# HBridges.net
KiCad netlist of a schematic drawn in Altium Designer
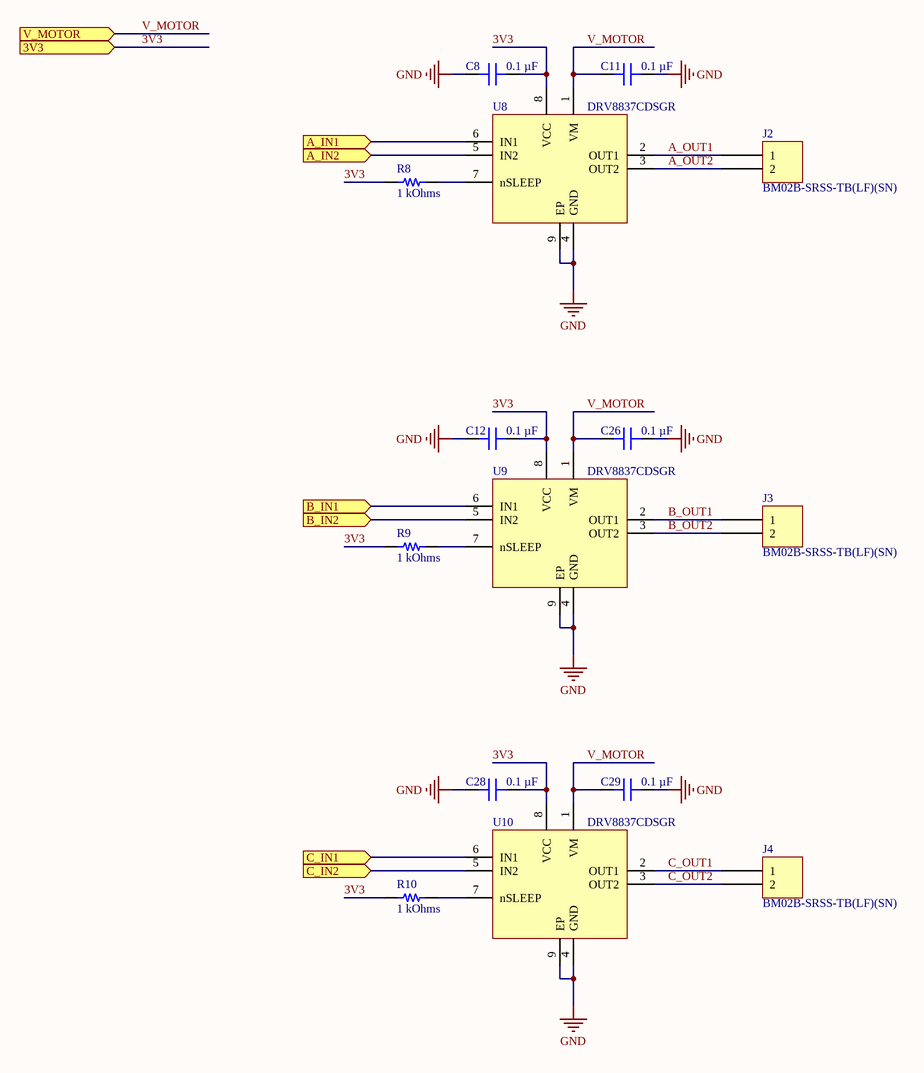
[diagram p0: HBridges.SchDoc]

(export (version "E")
  (design (tool "Eeschema 10.0.6"))
  (components
    (comp (ref "C8")
      (value "0.1 µF")
      (footprint "CAP 0402_1005")
      (description "CAP CER 0.1UF 16V X7R 0402")
      (fields (field (name "PART NUMBER") "C0402C104K4RACAUTO") (field (name "MANUFACTURER") "KEMET"))
      (libsource (lib "Celestial Altium Library - altium_library") (part "Capacitor"))
    )
    (comp (ref "C11")
      (value "0.1 µF")
      (footprint "CAP 0402_1005")
      (description "CAP CER 0.1UF 16V X7R 0402")
      (fields (field (name "PART NUMBER") "C0402C104K4RACAUTO") (field (name "MANUFACTURER") "KEMET"))
      (libsource (lib "Celestial Altium Library - altium_library") (part "Capacitor"))
    )
    (comp (ref "C12")
      (value "0.1 µF")
      (footprint "CAP 0402_1005")
      (description "CAP CER 0.1UF 16V X7R 0402")
      (fields (field (name "PART NUMBER") "C0402C104K4RACAUTO") (field (name "MANUFACTURER") "KEMET"))
      (libsource (lib "Celestial Altium Library - altium_library") (part "Capacitor"))
    )
    (comp (ref "C26")
      (value "0.1 µF")
      (footprint "CAP 0402_1005")
      (description "CAP CER 0.1UF 16V X7R 0402")
      (fields (field (name "PART NUMBER") "C0402C104K4RACAUTO") (field (name "MANUFACTURER") "KEMET"))
      (libsource (lib "Celestial Altium Library - altium_library") (part "Capacitor"))
    )
    (comp (ref "C28")
      (value "0.1 µF")
      (footprint "CAP 0402_1005")
      (description "CAP CER 0.1UF 16V X7R 0402")
      (fields (field (name "PART NUMBER") "C0402C104K4RACAUTO") (field (name "MANUFACTURER") "KEMET"))
      (libsource (lib "Celestial Altium Library - altium_library") (part "Capacitor"))
    )
    (comp (ref "C29")
      (value "0.1 µF")
      (footprint "CAP 0402_1005")
      (description "CAP CER 0.1UF 16V X7R 0402")
      (fields (field (name "PART NUMBER") "C0402C104K4RACAUTO") (field (name "MANUFACTURER") "KEMET"))
      (libsource (lib "Celestial Altium Library - altium_library") (part "Capacitor"))
    )
    (comp (ref "J2")
      (value "BM02B-SRSS-TB(LF)(SN)")
      (footprint "JST BM02B-SRSS-TB")
      (description "CONN HEADER SMD 2POS 1MM")
      (fields (field (name "MANUFACTURER") "JST Sales America Inc."))
      (libsource (lib "Celestial Altium Library - altium_library") (part "2 Pin"))
    )
    (comp (ref "J3")
      (value "BM02B-SRSS-TB(LF)(SN)")
      (footprint "JST BM02B-SRSS-TB")
      (description "CONN HEADER SMD 2POS 1MM")
      (fields (field (name "MANUFACTURER") "JST Sales America Inc."))
      (libsource (lib "Celestial Altium Library - altium_library") (part "2 Pin"))
    )
    (comp (ref "J4")
      (value "BM02B-SRSS-TB(LF)(SN)")
      (footprint "JST BM02B-SRSS-TB")
      (description "CONN HEADER SMD 2POS 1MM")
      (fields (field (name "MANUFACTURER") "JST Sales America Inc."))
      (libsource (lib "Celestial Altium Library - altium_library") (part "2 Pin"))
    )
    (comp (ref "R8")
      (value "1 kOhms")
      (footprint "YAGEO RES 0402_1005")
      (description "RES 1K OHM 1% 1/16W 0402")
      (fields (field (name "PART NUMBER") "RC0402FR-071KL") (field (name "MANUFACTURER") "Yageo"))
      (libsource (lib "Celestial Altium Library - altium_library") (part "Resistor"))
    )
    (comp (ref "R9")
      (value "1 kOhms")
      (footprint "YAGEO RES 0402_1005")
      (description "RES 1K OHM 1% 1/16W 0402")
      (fields (field (name "PART NUMBER") "RC0402FR-071KL") (field (name "MANUFACTURER") "Yageo"))
      (libsource (lib "Celestial Altium Library - altium_library") (part "Resistor"))
    )
    (comp (ref "R10")
      (value "1 kOhms")
      (footprint "YAGEO RES 0402_1005")
      (description "RES 1K OHM 1% 1/16W 0402")
      (fields (field (name "PART NUMBER") "RC0402FR-071KL") (field (name "MANUFACTURER") "Yageo"))
      (libsource (lib "Celestial Altium Library - altium_library") (part "Resistor"))
    )
    (comp (ref "U8")
      (value "DRV8837CDSGR")
      (footprint "SON50P200X200X80-9N")
      (description "11-V, 1-A H-bridge motor driver 8-WSON -40 to 85")
      (fields (field (name "MF") "Texas Instruments"))
      (libsource (lib "IC") (part "DRV8837CDSGR"))
    )
    (comp (ref "U9")
      (value "DRV8837CDSGR")
      (footprint "SON50P200X200X80-9N")
      (description "11-V, 1-A H-bridge motor driver 8-WSON -40 to 85")
      (fields (field (name "MF") "Texas Instruments"))
      (libsource (lib "IC") (part "DRV8837CDSGR"))
    )
    (comp (ref "U10")
      (value "DRV8837CDSGR")
      (footprint "SON50P200X200X80-9N")
      (description "11-V, 1-A H-bridge motor driver 8-WSON -40 to 85")
      (fields (field (name "MF") "Texas Instruments"))
      (libsource (lib "IC") (part "DRV8837CDSGR"))
    )
  )
  (nets
    (net (code "1") (name "/3V3") (class "Default")
      (node (ref "C12") (pin "1") (pinfunction "1_1") (pintype "passive"))
      (node (ref "C28") (pin "1") (pinfunction "1_1") (pintype "passive"))
      (node (ref "C8") (pin "1") (pinfunction "1_1") (pintype "passive"))
      (node (ref "R10") (pin "1") (pinfunction "1_1") (pintype "passive"))
      (node (ref "R8") (pin "1") (pinfunction "1_1") (pintype "passive"))
      (node (ref "R9") (pin "1") (pinfunction "1_1") (pintype "passive"))
      (node (ref "U10") (pin "8") (pinfunction "VCC_8") (pintype "passive"))
      (node (ref "U8") (pin "8") (pinfunction "VCC_8") (pintype "passive"))
      (node (ref "U9") (pin "8") (pinfunction "VCC_8") (pintype "passive"))
    )
    (net (code "2") (name "/A_IN1") (class "Default")
      (node (ref "U8") (pin "6") (pinfunction "IN1_6") (pintype "passive"))
    )
    (net (code "3") (name "/A_IN2") (class "Default")
      (node (ref "U8") (pin "5") (pinfunction "IN2_5") (pintype "passive"))
    )
    (net (code "4") (name "/A_OUT1") (class "Default")
      (node (ref "J2") (pin "1") (pinfunction "1_1") (pintype "passive"))
      (node (ref "U8") (pin "2") (pinfunction "OUT1_2") (pintype "passive"))
    )
    (net (code "5") (name "/A_OUT2") (class "Default")
      (node (ref "J2") (pin "2") (pinfunction "2_2") (pintype "passive"))
      (node (ref "U8") (pin "3") (pinfunction "OUT2_3") (pintype "passive"))
    )
    (net (code "6") (name "/B_IN1") (class "Default")
      (node (ref "U9") (pin "6") (pinfunction "IN1_6") (pintype "passive"))
    )
    (net (code "7") (name "/B_IN2") (class "Default")
      (node (ref "U9") (pin "5") (pinfunction "IN2_5") (pintype "passive"))
    )
    (net (code "8") (name "/B_OUT1") (class "Default")
      (node (ref "J3") (pin "1") (pinfunction "1_1") (pintype "passive"))
      (node (ref "U9") (pin "2") (pinfunction "OUT1_2") (pintype "passive"))
    )
    (net (code "9") (name "/B_OUT2") (class "Default")
      (node (ref "J3") (pin "2") (pinfunction "2_2") (pintype "passive"))
      (node (ref "U9") (pin "3") (pinfunction "OUT2_3") (pintype "passive"))
    )
    (net (code "10") (name "/C_IN1") (class "Default")
      (node (ref "U10") (pin "6") (pinfunction "IN1_6") (pintype "passive"))
    )
    (net (code "11") (name "/C_IN2") (class "Default")
      (node (ref "U10") (pin "5") (pinfunction "IN2_5") (pintype "passive"))
    )
    (net (code "12") (name "/C_OUT1") (class "Default")
      (node (ref "J4") (pin "1") (pinfunction "1_1") (pintype "passive"))
      (node (ref "U10") (pin "2") (pinfunction "OUT1_2") (pintype "passive"))
    )
    (net (code "13") (name "/C_OUT2") (class "Default")
      (node (ref "J4") (pin "2") (pinfunction "2_2") (pintype "passive"))
      (node (ref "U10") (pin "3") (pinfunction "OUT2_3") (pintype "passive"))
    )
    (net (code "14") (name "/V_MOTOR") (class "Default")
      (node (ref "C11") (pin "2") (pinfunction "2_2") (pintype "passive"))
      (node (ref "C26") (pin "2") (pinfunction "2_2") (pintype "passive"))
      (node (ref "C29") (pin "2") (pinfunction "2_2") (pintype "passive"))
      (node (ref "U10") (pin "1") (pinfunction "VM_1") (pintype "passive"))
      (node (ref "U8") (pin "1") (pinfunction "VM_1") (pintype "passive"))
      (node (ref "U9") (pin "1") (pinfunction "VM_1") (pintype "passive"))
    )
    (net (code "15") (name "GND") (class "Default")
      (node (ref "C11") (pin "1") (pinfunction "1_1") (pintype "passive"))
      (node (ref "C12") (pin "2") (pinfunction "2_2") (pintype "passive"))
      (node (ref "C26") (pin "1") (pinfunction "1_1") (pintype "passive"))
      (node (ref "C28") (pin "2") (pinfunction "2_2") (pintype "passive"))
      (node (ref "C29") (pin "1") (pinfunction "1_1") (pintype "passive"))
      (node (ref "C8") (pin "2") (pinfunction "2_2") (pintype "passive"))
      (node (ref "U10") (pin "4") (pinfunction "GND_4") (pintype "passive"))
      (node (ref "U10") (pin "9") (pinfunction "EP_9") (pintype "passive"))
      (node (ref "U8") (pin "4") (pinfunction "GND_4") (pintype "passive"))
      (node (ref "U8") (pin "9") (pinfunction "EP_9") (pintype "passive"))
      (node (ref "U9") (pin "4") (pinfunction "GND_4") (pintype "passive"))
      (node (ref "U9") (pin "9") (pinfunction "EP_9") (pintype "passive"))
    )
    (net (code "16") (name "Net-(U8-nSLEEP)") (class "Default")
      (node (ref "R8") (pin "2") (pinfunction "2_2") (pintype "passive"))
      (node (ref "U8") (pin "7") (pinfunction "nSLEEP_7") (pintype "passive"))
    )
    (net (code "17") (name "Net-(U9-nSLEEP)") (class "Default")
      (node (ref "R9") (pin "2") (pinfunction "2_2") (pintype "passive"))
      (node (ref "U9") (pin "7") (pinfunction "nSLEEP_7") (pintype "passive"))
    )
    (net (code "18") (name "Net-(U10-nSLEEP)") (class "Default")
      (node (ref "R10") (pin "2") (pinfunction "2_2") (pintype "passive"))
      (node (ref "U10") (pin "7") (pinfunction "nSLEEP_7") (pintype "passive"))
    )
  )
)
